# MainSheet.net
KiCad netlist of a schematic drawn in Altium Designer
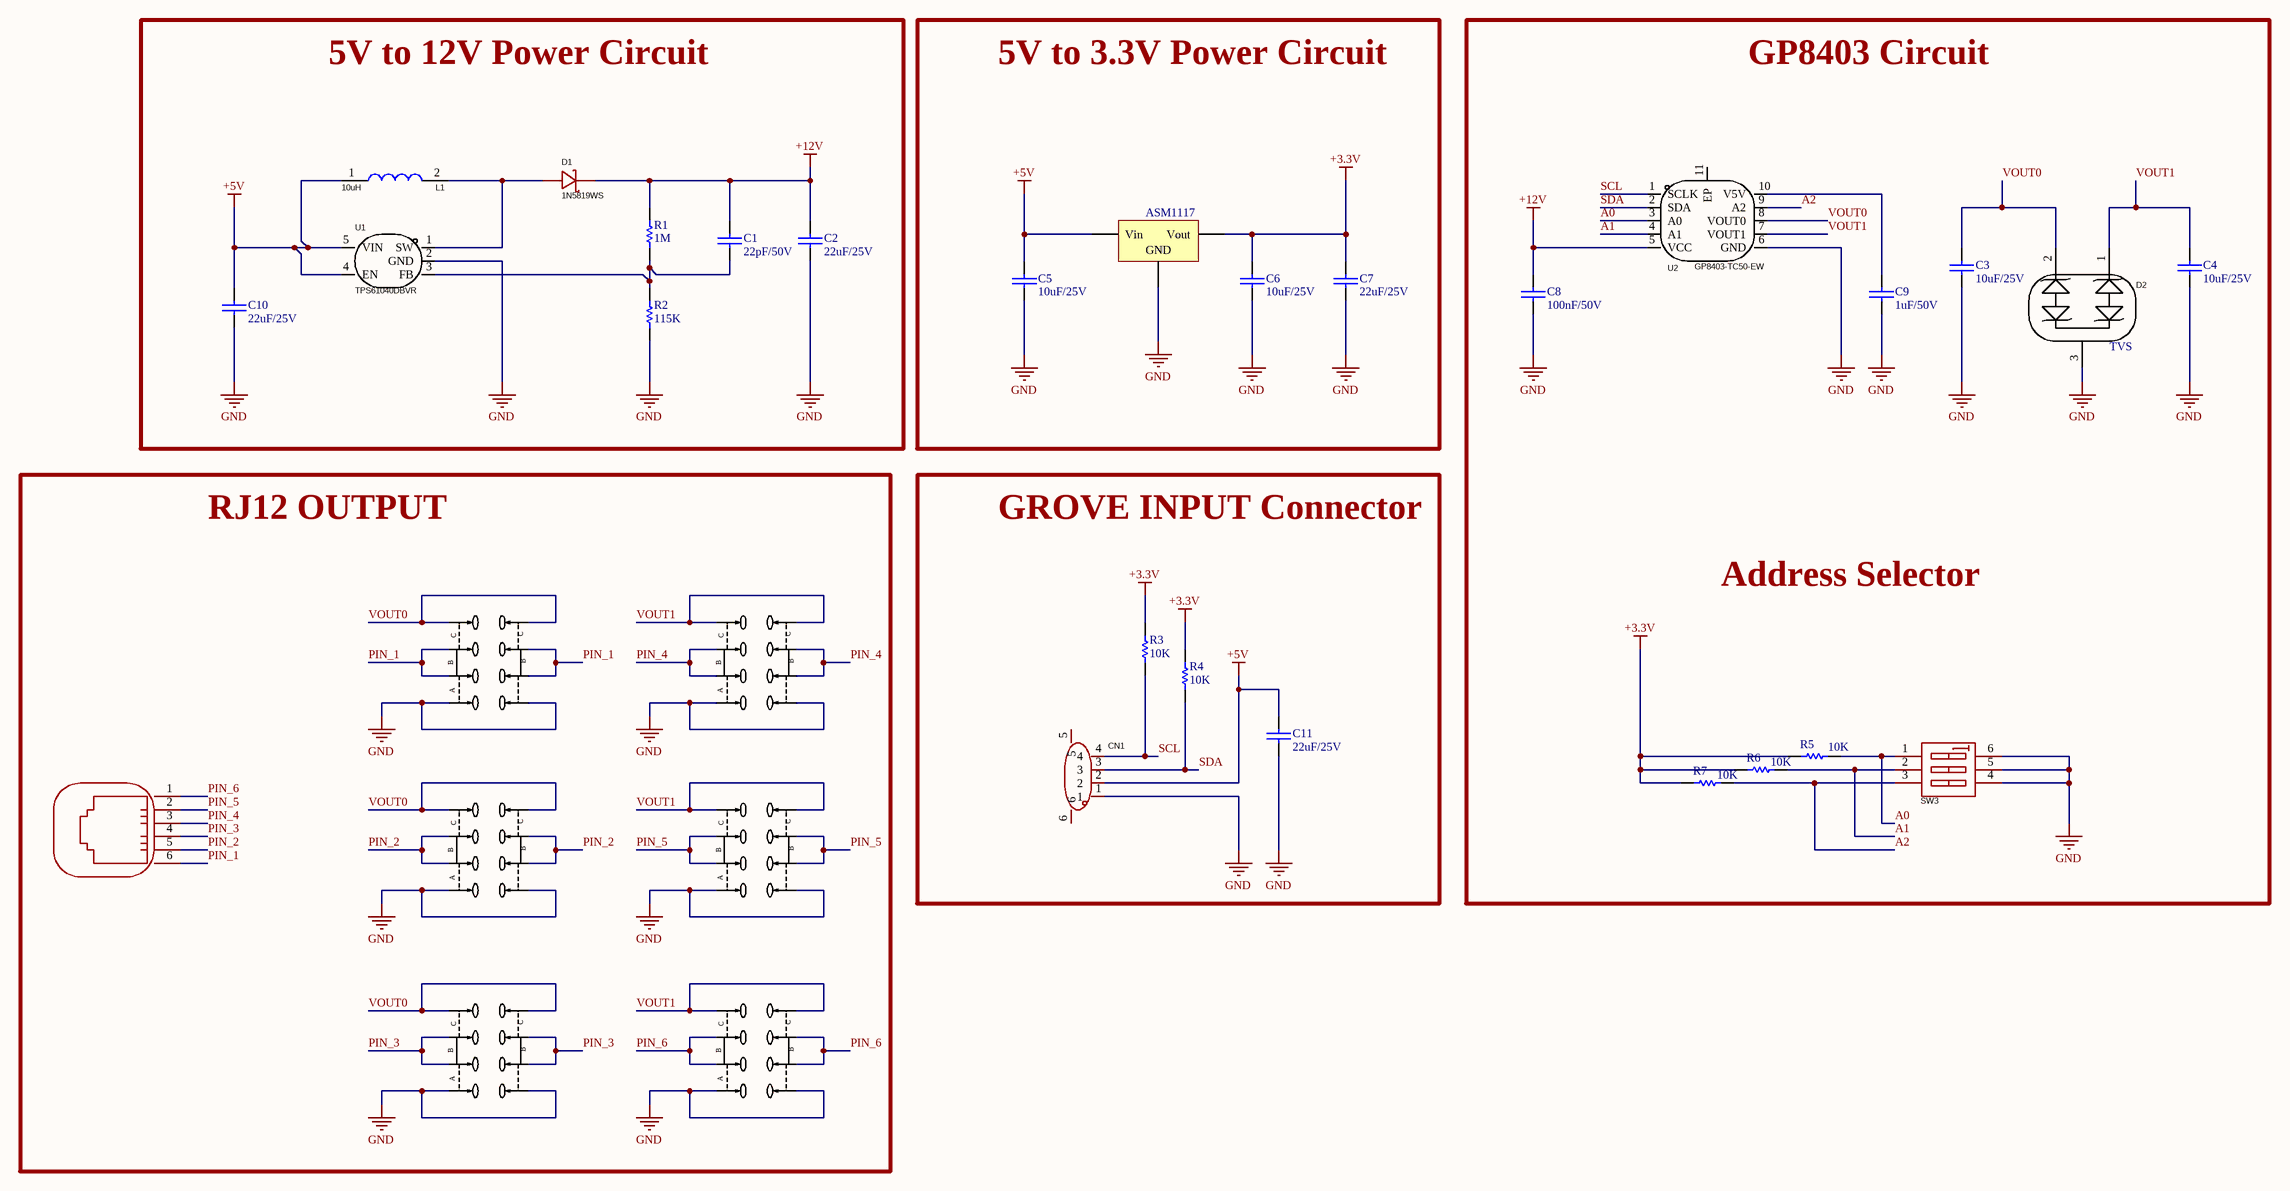
[diagram p0: MainSheet.SchDoc]

(export (version "E")
  (design (tool "Eeschema 10.0.6"))
  (components
    (comp (ref "ASM1117")
      (value "AMS1117 - 3.3V Reg")
      (footprint "SOT229P700X180-4N")
      (description "C6186")
      (fields (field (name "CREATED BY") "NourAldin"))
      (libsource (lib "AMS1117 - 3.3V Reg") (part "AMS1117 - 3.3V Reg"))
    )
    (comp (ref "C1")
      (value "22pF/50V")
      (footprint "CAPC2012X08N")
      (description "C105623")
      (fields (field (name "CREATEDBY") "NourAldin"))
      (libsource (lib "0805 Capacitor") (part "0805 capacitor"))
    )
    (comp (ref "C2")
      (value "22uF/25V")
      (footprint "CAPC2012X08N")
      (description "C602037")
      (fields (field (name "CREATEDBY") "NourAldin"))
      (libsource (lib "0805 Capacitor") (part "0805 capacitor"))
    )
    (comp (ref "C3")
      (value "10uF/25V")
      (footprint "CAPC2012X08N")
      (description "C15850")
      (fields (field (name "CREATEDBY") "NourAldin"))
      (libsource (lib "0805 Capacitor") (part "0805 capacitor"))
    )
    (comp (ref "C4")
      (value "10uF/25V")
      (footprint "CAPC2012X08N")
      (description "C15850")
      (fields (field (name "CREATEDBY") "NourAldin"))
      (libsource (lib "0805 Capacitor") (part "0805 capacitor"))
    )
    (comp (ref "C5")
      (value "10uF/25V")
      (footprint "CAPC2012X08N")
      (description "C15850")
      (fields (field (name "CREATEDBY") "NourAldin"))
      (libsource (lib "0805 Capacitor") (part "0805 capacitor"))
    )
    (comp (ref "C6")
      (value "10uF/25V")
      (footprint "CAPC2012X08N")
      (description "C15850")
      (fields (field (name "CREATEDBY") "NourAldin"))
      (libsource (lib "0805 Capacitor") (part "0805 capacitor"))
    )
    (comp (ref "C7")
      (value "22uF/25V")
      (footprint "CAPC2012X08N")
      (description "C602037")
      (fields (field (name "CREATEDBY") "NourAldin"))
      (libsource (lib "0805 Capacitor") (part "0805 capacitor"))
    )
    (comp (ref "C8")
      (value "100nF/50V")
      (footprint "CAPC2012X08N")
      (description "C49678")
      (fields (field (name "CREATEDBY") "NourAldin"))
      (libsource (lib "0805 Capacitor") (part "0805 capacitor"))
    )
    (comp (ref "C9")
      (value "1uF/50V")
      (footprint "CAPC2012X08N")
      (description "C28323")
      (fields (field (name "CREATEDBY") "NourAldin"))
      (libsource (lib "0805 Capacitor") (part "0805 capacitor"))
    )
    (comp (ref "C10")
      (value "22uF/25V")
      (footprint "CAPC2012X08N")
      (description "C602037")
      (fields (field (name "CREATEDBY") "NourAldin"))
      (libsource (lib "0805 Capacitor") (part "0805 capacitor"))
    )
    (comp (ref "C11")
      (value "22uF/25V")
      (footprint "CAPC2012X08N")
      (description "C602037")
      (fields (field (name "CREATEDBY") "NourAldin"))
      (libsource (lib "0805 Capacitor") (part "0805 capacitor"))
    )
    (comp (ref "CN1")
      (value "ZX-HY2.0-4PWT")
      (footprint "CONN-SMD_4P-P2.00_ZX-HY2.0-4PWT")
      (description "C7429571")
      (fields (field (name "MANUFACTURER") "Megastar(兆星)"))
      (libsource (lib "LIB") (part "ZX-HY2.0-4PWT"))
    )
    (comp (ref "D1")
      (value "1N5819WS")
      (footprint "SOD-323_L1.8-W1.3-LS2.5-RD")
      (description "C191023")
      (fields (field (name "MANUFACTURER") "Hottech(合科泰)"))
      (libsource (lib "LIB") (part "1N5819WS_C191023"))
    )
    (comp (ref "D2")
      (value "TVS")
      (footprint "SOT-23_L2.9-W1.3-P1.90-LS2.4-BR")
      (description "C2892527")
      (fields
        (field (name "MANUFACTURER") "Littelfuse(美国力特)")
        (field (name "MANUFACTURER PART") "SM712-02HTG")
      )
      (libsource (lib "DIVERSE") (part "TVS 2 Channel"))
    )
    (comp (ref "L1")
      (value "10uH")
      (footprint "IND-SMD_L4.5-W4.5_SMMS0420")
      (description "C133195")
      (fields (field (name "MANUFACTURER") "SXN(顺翔诺)") (field (name "MANUFACTURER PART") "SMMS0420-100M"))
      (libsource (lib "LIB") (part "SMMS0420-100M"))
    )
    (comp (ref "R1")
      (value "1M")
      (footprint "RESC2012X07N")
      (description "C107700")
      (fields (field (name "CREATED BY") "NourAldin"))
      (libsource (lib "0805 Resistor") (part "0805 Resistor"))
    )
    (comp (ref "R2")
      (value "115K")
      (footprint "RESC2012X07N")
      (description "C2933289")
      (fields (field (name "CREATED BY") "NourAldin"))
      (libsource (lib "0805 Resistor") (part "0805 Resistor"))
    )
    (comp (ref "R3")
      (value "10K")
      (footprint "RESC2012X07N")
      (description "C84376")
      (fields (field (name "CREATED BY") "NourAldin"))
      (libsource (lib "0805 Resistor") (part "0805 Resistor"))
    )
    (comp (ref "R4")
      (value "10K")
      (footprint "RESC2012X07N")
      (description "C84376")
      (fields (field (name "CREATED BY") "NourAldin"))
      (libsource (lib "0805 Resistor") (part "0805 Resistor"))
    )
    (comp (ref "R5")
      (value "10K")
      (footprint "RESC2012X07N")
      (description "C84376")
      (fields (field (name "CREATED BY") "NourAldin"))
      (libsource (lib "0805 Resistor") (part "0805 Resistor"))
    )
    (comp (ref "R6")
      (value "10K")
      (footprint "RESC2012X07N")
      (description "C84376")
      (fields (field (name "CREATED BY") "NourAldin"))
      (libsource (lib "0805 Resistor") (part "0805 Resistor"))
    )
    (comp (ref "R7")
      (value "10K")
      (footprint "RESC2012X07N")
      (description "C84376")
      (fields (field (name "CREATED BY") "NourAldin"))
      (libsource (lib "0805 Resistor") (part "0805 Resistor"))
    )
    (comp (ref "SW1")
      (value "MST23D19G2")
      (footprint "SW-SMD_MST23D19G2")
      (description "C431545")
      (fields (field (name "MANUFACTURER") "SHOU HAN(首韩)"))
      (libsource (lib "LIB") (part "MST23D19G2"))
    )
    (comp (ref "SW2")
      (value "MST23D19G2")
      (footprint "SW-SMD_MST23D19G2")
      (description "C431545")
      (fields (field (name "MANUFACTURER") "SHOU HAN(首韩)"))
      (libsource (lib "LIB") (part "MST23D19G2"))
    )
    (comp (ref "SW3")
      (value "DSHP03TS-S")
      (footprint "SW-SMD_DSHP03TS-S")
      (description "C319051")
      (fields (field (name "MANUFACTURER") "XKB Connection(中国星坤)"))
      (libsource (lib "LIB") (part "DSHP03TS-S"))
    )
    (comp (ref "SW4")
      (value "MST23D19G2")
      (footprint "SW-SMD_MST23D19G2")
      (description "C431545")
      (fields (field (name "MANUFACTURER") "SHOU HAN(首韩)"))
      (libsource (lib "LIB") (part "MST23D19G2"))
    )
    (comp (ref "SW5")
      (value "MST23D19G2")
      (footprint "SW-SMD_MST23D19G2")
      (description "C431545")
      (fields (field (name "MANUFACTURER") "SHOU HAN(首韩)"))
      (libsource (lib "LIB") (part "MST23D19G2"))
    )
    (comp (ref "SW6")
      (value "MST23D19G2")
      (footprint "SW-SMD_MST23D19G2")
      (description "C431545")
      (fields (field (name "MANUFACTURER") "SHOU HAN(首韩)"))
      (libsource (lib "LIB") (part "MST23D19G2"))
    )
    (comp (ref "SW7")
      (value "MST23D19G2")
      (footprint "SW-SMD_MST23D19G2")
      (description "C431545")
      (fields (field (name "MANUFACTURER") "SHOU HAN(首韩)"))
      (libsource (lib "LIB") (part "MST23D19G2"))
    )
    (comp (ref "U1")
      (value "TPS61040DBVR")
      (footprint "SOT-23-5_L3.0-W1.7-P0.95-LS2.8-BL")
      (description "C7722")
      (fields (field (name "MANUFACTURER") "TI(德州仪器)"))
      (libsource (lib "LIB") (part "TPS61040DBVR"))
    )
    (comp (ref "U2")
      (value "GP8403-TC50-EW")
      (footprint "ESSOP-10_L4.9-W3.9-P1.00-LS6.0-BL-EP")
      (description "C3152007")
      (fields (field (name "MANUFACTURER") "Guestgood(客益)"))
      (libsource (lib "LIB") (part "GP8403-TC50-EW"))
    )
    (comp (ref "U3")
      (value "DS1133-S60BPX")
      (footprint "RJ11-TH_DS1133-S60BPX")
      (description "C77859")
      (fields (field (name "MANUFACTURER") "CONNFLY"))
      (libsource (lib "LIB") (part "DS1133-S60BPX"))
    )
  )
  (nets
    (net (code "1") (name "+3.3V") (class "Default")
      (node (ref "ASM1117") (pin "Vout") (pinfunction "Vout_Vout") (pintype "passive"))
      (node (ref "C6") (pin "2") (pinfunction "2_2") (pintype "passive"))
      (node (ref "C7") (pin "2") (pinfunction "2_2") (pintype "passive"))
      (node (ref "R3") (pin "2") (pinfunction "2_2") (pintype "passive"))
      (node (ref "R4") (pin "2") (pinfunction "2_2") (pintype "passive"))
      (node (ref "R5") (pin "2") (pinfunction "2_2") (pintype "passive"))
      (node (ref "R6") (pin "2") (pinfunction "2_2") (pintype "passive"))
      (node (ref "R7") (pin "2") (pinfunction "2_2") (pintype "passive"))
    )
    (net (code "2") (name "+5V") (class "Default")
      (node (ref "ASM1117") (pin "Vin") (pinfunction "Vin_Vin") (pintype "passive"))
      (node (ref "C10") (pin "2") (pinfunction "2_2") (pintype "passive"))
      (node (ref "C11") (pin "2") (pinfunction "2_2") (pintype "passive"))
      (node (ref "C5") (pin "2") (pinfunction "2_2") (pintype "passive"))
      (node (ref "CN1") (pin "2") (pinfunction "2_2") (pintype "passive"))
      (node (ref "L1") (pin "1") (pinfunction "1_1") (pintype "passive"))
      (node (ref "U1") (pin "4") (pinfunction "EN_4") (pintype "passive"))
      (node (ref "U1") (pin "5") (pinfunction "VIN_5") (pintype "passive"))
    )
    (net (code "3") (name "+12V") (class "Default")
      (node (ref "C1") (pin "2") (pinfunction "2_2") (pintype "passive"))
      (node (ref "C2") (pin "2") (pinfunction "2_2") (pintype "passive"))
      (node (ref "C8") (pin "2") (pinfunction "2_2") (pintype "passive"))
      (node (ref "D1") (pin "1") (pinfunction "K_1") (pintype "passive"))
      (node (ref "R1") (pin "2") (pinfunction "2_2") (pintype "passive"))
      (node (ref "U2") (pin "5") (pinfunction "VCC_5") (pintype "passive"))
    )
    (net (code "4") (name "/A0") (class "Default")
      (node (ref "R5") (pin "1") (pinfunction "1_1") (pintype "passive"))
      (node (ref "SW3") (pin "1") (pinfunction "1_1") (pintype "passive"))
      (node (ref "U2") (pin "3") (pinfunction "A0_3") (pintype "passive"))
    )
    (net (code "5") (name "/A1") (class "Default")
      (node (ref "R6") (pin "1") (pinfunction "1_1") (pintype "passive"))
      (node (ref "SW3") (pin "2") (pinfunction "2_2") (pintype "passive"))
      (node (ref "U2") (pin "4") (pinfunction "A1_4") (pintype "passive"))
    )
    (net (code "6") (name "/A2") (class "Default")
      (node (ref "R7") (pin "1") (pinfunction "1_1") (pintype "passive"))
      (node (ref "SW3") (pin "3") (pinfunction "3_3") (pintype "passive"))
      (node (ref "U2") (pin "9") (pinfunction "A2_9") (pintype "passive"))
    )
    (net (code "7") (name "/PIN_1") (class "Default")
      (node (ref "SW1") (pin "2") (pinfunction "2_2") (pintype "passive"))
      (node (ref "SW1") (pin "3") (pinfunction "3_3") (pintype "passive"))
      (node (ref "SW1") (pin "6") (pinfunction "6_6") (pintype "passive"))
      (node (ref "SW1") (pin "7") (pinfunction "7_7") (pintype "passive"))
      (node (ref "U3") (pin "6") (pinfunction "6_6") (pintype "passive"))
    )
    (net (code "8") (name "/PIN_2") (class "Default")
      (node (ref "SW4") (pin "2") (pinfunction "2_2") (pintype "passive"))
      (node (ref "SW4") (pin "3") (pinfunction "3_3") (pintype "passive"))
      (node (ref "SW4") (pin "6") (pinfunction "6_6") (pintype "passive"))
      (node (ref "SW4") (pin "7") (pinfunction "7_7") (pintype "passive"))
      (node (ref "U3") (pin "5") (pinfunction "5_5") (pintype "passive"))
    )
    (net (code "9") (name "/PIN_3") (class "Default")
      (node (ref "SW6") (pin "2") (pinfunction "2_2") (pintype "passive"))
      (node (ref "SW6") (pin "3") (pinfunction "3_3") (pintype "passive"))
      (node (ref "SW6") (pin "6") (pinfunction "6_6") (pintype "passive"))
      (node (ref "SW6") (pin "7") (pinfunction "7_7") (pintype "passive"))
      (node (ref "U3") (pin "4") (pinfunction "4_4") (pintype "passive"))
    )
    (net (code "10") (name "/PIN_4") (class "Default")
      (node (ref "SW2") (pin "2") (pinfunction "2_2") (pintype "passive"))
      (node (ref "SW2") (pin "3") (pinfunction "3_3") (pintype "passive"))
      (node (ref "SW2") (pin "6") (pinfunction "6_6") (pintype "passive"))
      (node (ref "SW2") (pin "7") (pinfunction "7_7") (pintype "passive"))
      (node (ref "U3") (pin "3") (pinfunction "3_3") (pintype "passive"))
    )
    (net (code "11") (name "/PIN_5") (class "Default")
      (node (ref "SW5") (pin "2") (pinfunction "2_2") (pintype "passive"))
      (node (ref "SW5") (pin "3") (pinfunction "3_3") (pintype "passive"))
      (node (ref "SW5") (pin "6") (pinfunction "6_6") (pintype "passive"))
      (node (ref "SW5") (pin "7") (pinfunction "7_7") (pintype "passive"))
      (node (ref "U3") (pin "2") (pinfunction "2_2") (pintype "passive"))
    )
    (net (code "12") (name "/PIN_6") (class "Default")
      (node (ref "SW7") (pin "2") (pinfunction "2_2") (pintype "passive"))
      (node (ref "SW7") (pin "3") (pinfunction "3_3") (pintype "passive"))
      (node (ref "SW7") (pin "6") (pinfunction "6_6") (pintype "passive"))
      (node (ref "SW7") (pin "7") (pinfunction "7_7") (pintype "passive"))
      (node (ref "U3") (pin "1") (pinfunction "1_1") (pintype "passive"))
    )
    (net (code "13") (name "/SCL") (class "Default")
      (node (ref "CN1") (pin "4") (pinfunction "4_4") (pintype "passive"))
      (node (ref "R3") (pin "1") (pinfunction "1_1") (pintype "passive"))
      (node (ref "U2") (pin "1") (pinfunction "SCLK_1") (pintype "passive"))
    )
    (net (code "14") (name "/SDA") (class "Default")
      (node (ref "CN1") (pin "3") (pinfunction "3_3") (pintype "passive"))
      (node (ref "R4") (pin "1") (pinfunction "1_1") (pintype "passive"))
      (node (ref "U2") (pin "2") (pinfunction "SDA_2") (pintype "passive"))
    )
    (net (code "15") (name "/VOUT0") (class "Default")
      (node (ref "C3") (pin "2") (pinfunction "2_2") (pintype "passive"))
      (node (ref "D2") (pin "2") (pinfunction "2_2") (pintype "passive"))
      (node (ref "SW1") (pin "4") (pinfunction "4_4") (pintype "passive"))
      (node (ref "SW1") (pin "5") (pinfunction "5_5") (pintype "passive"))
      (node (ref "SW4") (pin "4") (pinfunction "4_4") (pintype "passive"))
      (node (ref "SW4") (pin "5") (pinfunction "5_5") (pintype "passive"))
      (node (ref "SW6") (pin "4") (pinfunction "4_4") (pintype "passive"))
      (node (ref "SW6") (pin "5") (pinfunction "5_5") (pintype "passive"))
      (node (ref "U2") (pin "8") (pinfunction "VOUT0_8") (pintype "passive"))
    )
    (net (code "16") (name "/VOUT1") (class "Default")
      (node (ref "C4") (pin "2") (pinfunction "2_2") (pintype "passive"))
      (node (ref "D2") (pin "1") (pinfunction "1_1") (pintype "passive"))
      (node (ref "SW2") (pin "4") (pinfunction "4_4") (pintype "passive"))
      (node (ref "SW2") (pin "5") (pinfunction "5_5") (pintype "passive"))
      (node (ref "SW5") (pin "4") (pinfunction "4_4") (pintype "passive"))
      (node (ref "SW5") (pin "5") (pinfunction "5_5") (pintype "passive"))
      (node (ref "SW7") (pin "4") (pinfunction "4_4") (pintype "passive"))
      (node (ref "SW7") (pin "5") (pinfunction "5_5") (pintype "passive"))
      (node (ref "U2") (pin "7") (pinfunction "VOUT1_7") (pintype "passive"))
    )
    (net (code "17") (name "GND") (class "Default")
      (node (ref "ASM1117") (pin "GND") (pinfunction "GND_GND") (pintype "passive"))
      (node (ref "C10") (pin "1") (pinfunction "1_1") (pintype "passive"))
      (node (ref "C11") (pin "1") (pinfunction "1_1") (pintype "passive"))
      (node (ref "C2") (pin "1") (pinfunction "1_1") (pintype "passive"))
      (node (ref "C3") (pin "1") (pinfunction "1_1") (pintype "passive"))
      (node (ref "C4") (pin "1") (pinfunction "1_1") (pintype "passive"))
      (node (ref "C5") (pin "1") (pinfunction "1_1") (pintype "passive"))
      (node (ref "C6") (pin "1") (pinfunction "1_1") (pintype "passive"))
      (node (ref "C7") (pin "1") (pinfunction "1_1") (pintype "passive"))
      (node (ref "C8") (pin "1") (pinfunction "1_1") (pintype "passive"))
      (node (ref "C9") (pin "1") (pinfunction "1_1") (pintype "passive"))
      (node (ref "CN1") (pin "1") (pinfunction "1_1") (pintype "passive"))
      (node (ref "D2") (pin "3") (pinfunction "3_3") (pintype "passive"))
      (node (ref "R2") (pin "1") (pinfunction "1_1") (pintype "passive"))
      (node (ref "SW1") (pin "1") (pinfunction "1_1") (pintype "passive"))
      (node (ref "SW1") (pin "8") (pinfunction "8_8") (pintype "passive"))
      (node (ref "SW2") (pin "1") (pinfunction "1_1") (pintype "passive"))
      (node (ref "SW2") (pin "8") (pinfunction "8_8") (pintype "passive"))
      (node (ref "SW3") (pin "4") (pinfunction "4_4") (pintype "passive"))
      (node (ref "SW3") (pin "5") (pinfunction "5_5") (pintype "passive"))
      (node (ref "SW3") (pin "6") (pinfunction "6_6") (pintype "passive"))
      (node (ref "SW4") (pin "1") (pinfunction "1_1") (pintype "passive"))
      (node (ref "SW4") (pin "8") (pinfunction "8_8") (pintype "passive"))
      (node (ref "SW5") (pin "1") (pinfunction "1_1") (pintype "passive"))
      (node (ref "SW5") (pin "8") (pinfunction "8_8") (pintype "passive"))
      (node (ref "SW6") (pin "1") (pinfunction "1_1") (pintype "passive"))
      (node (ref "SW6") (pin "8") (pinfunction "8_8") (pintype "passive"))
      (node (ref "SW7") (pin "1") (pinfunction "1_1") (pintype "passive"))
      (node (ref "SW7") (pin "8") (pinfunction "8_8") (pintype "passive"))
      (node (ref "U1") (pin "2") (pinfunction "GND_2") (pintype "passive"))
      (node (ref "U2") (pin "6") (pinfunction "GND_6") (pintype "passive"))
    )
    (net (code "18") (name "Net-(D1-A)") (class "Default")
      (node (ref "D1") (pin "2") (pinfunction "A_2") (pintype "passive"))
      (node (ref "L1") (pin "2") (pinfunction "2_2") (pintype "passive"))
      (node (ref "U1") (pin "1") (pinfunction "SW_1") (pintype "passive"))
    )
    (net (code "19") (name "Net-(U1-FB)") (class "Default")
      (node (ref "C1") (pin "1") (pinfunction "1_1") (pintype "passive"))
      (node (ref "R1") (pin "1") (pinfunction "1_1") (pintype "passive"))
      (node (ref "R2") (pin "2") (pinfunction "2_2") (pintype "passive"))
      (node (ref "U1") (pin "3") (pinfunction "FB_3") (pintype "passive"))
    )
    (net (code "20") (name "Net-(U2-V5V)") (class "Default")
      (node (ref "C9") (pin "2") (pinfunction "2_2") (pintype "passive"))
      (node (ref "U2") (pin "10") (pinfunction "V5V_10") (pintype "passive"))
    )
    (net (code "21") (name "unconnected-(CN1-Pad5)") (class "Default")
      (node (ref "CN1") (pin "5") (pinfunction "5_5") (pintype "passive"))
    )
    (net (code "22") (name "unconnected-(CN1-Pad6)") (class "Default")
      (node (ref "CN1") (pin "6") (pinfunction "6_6") (pintype "passive"))
    )
    (net (code "23") (name "unconnected-(U2-EP-Pad11)") (class "Default")
      (node (ref "U2") (pin "11") (pinfunction "EP_11") (pintype "passive"))
    )
  )
)
